# ATtinyBoard.net
KiCad netlist of a schematic drawn in EAGLE
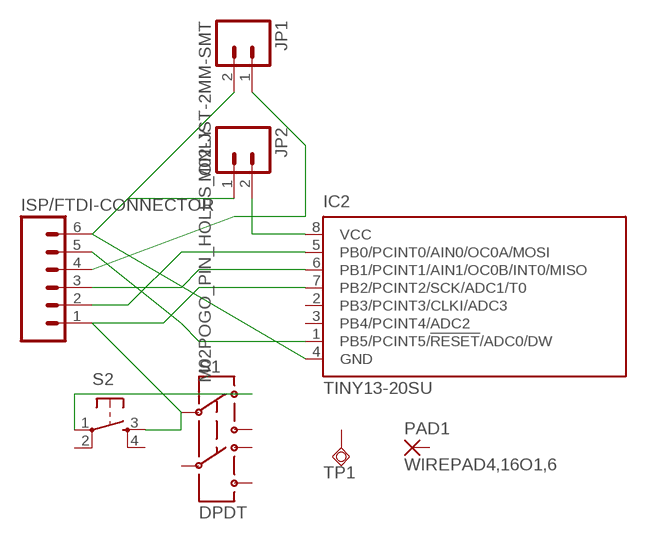
[diagram p0: schematic, sheet 1]

(export (version "E")
  (design (tool "Eeschema 10.0.6"))
  (components
    (comp (ref "IC2")
      (value "TINY13-20SU")
      (footprint "eagle-import:8S2")
      (fields (field (name "MPN") "ATTINY13-20SU"))
      (libsource (lib "eagle-import") (part "TINY13SU-20"))
    )
    (comp (ref "ISP/FTDI-CONNECTOR")
      (value "M06SMD")
      (footprint "eagle-import:1X06-SMD")
      (libsource (lib "eagle-import") (part "M06SMD"))
    )
    (comp (ref "JP1")
      (value "M02-JST-2MM-SMT")
      (footprint "eagle-import:JST-2-SMD")
      (libsource (lib "eagle-import") (part "M02-JST-2MM-SMT"))
    )
    (comp (ref "JP2")
      (value "M02POGO_PIN_HOLES_ONLY")
      (footprint "eagle-import:1X02_PP_HOLES_ONLY")
      (libsource (lib "eagle-import") (part "M02POGO_PIN_HOLES_ONLY"))
    )
    (comp (ref "PAD1")
      (value "WIREPAD4,16O1,6")
      (footprint "eagle-import:4,16O1,6")
      (libsource (lib "eagle-import") (part "WIREPAD4,16O1,6"))
    )
    (comp (ref "S1")
      (value "DPDT")
      (footprint "eagle-import:AYZ0202")
      (libsource (lib "eagle-import") (part "SWITCH-DPDTAYZ0202"))
    )
    (comp (ref "S2")
      (value "TAC_SWITCHSMD")
      (footprint "eagle-import:TACTILE_SWITCH_SMD")
      (libsource (lib "eagle-import") (part "TAC_SWITCHSMD"))
    )
    (comp (ref "TP1")
      (value "TPSQTP20R")
      (footprint "eagle-import:TP20R")
      (libsource (lib "eagle-import") (part "TPSQTP20R"))
    )
  )
  (nets
    (net (code "1") (name "Net-(IC2-GND)") (class "Default")
      (node (ref "IC2") (pin "4") (pinfunction "GND_4") (pintype "power_in"))
      (node (ref "ISP/FTDI-CONNECTOR") (pin "6") (pinfunction "6_6") (pintype "passive"))
      (node (ref "JP1") (pin "2") (pinfunction "1_2") (pintype "passive"))
      (node (ref "JP2") (pin "1") (pinfunction "1_1") (pintype "passive"))
    )
    (net (code "2") (name "Net-(IC2-PB0{slash}PCINT0{slash}AIN0{slash}OC0A{slash}MOSI)") (class "Default")
      (node (ref "IC2") (pin "5") (pinfunction "PB0/PCINT0/AIN0/OC0A/MOSI_5") (pintype "bidirectional"))
      (node (ref "ISP/FTDI-CONNECTOR") (pin "2") (pinfunction "2_2") (pintype "passive"))
    )
    (net (code "3") (name "Net-(IC2-PB1{slash}PCINT1{slash}AIN1{slash}OC0B{slash}INT0{slash}MISO)") (class "Default")
      (node (ref "IC2") (pin "6") (pinfunction "PB1/PCINT1/AIN1/OC0B/INT0/MISO_6") (pintype "bidirectional"))
      (node (ref "ISP/FTDI-CONNECTOR") (pin "3") (pinfunction "3_3") (pintype "passive"))
    )
    (net (code "4") (name "Net-(IC2-PB2{slash}PCINT2{slash}SCK{slash}ADC1{slash}T0)") (class "Default")
      (node (ref "IC2") (pin "7") (pinfunction "PB2/PCINT2/SCK/ADC1/T0_7") (pintype "bidirectional"))
      (node (ref "ISP/FTDI-CONNECTOR") (pin "1") (pinfunction "1_1") (pintype "passive"))
      (node (ref "S1") (pin "2") (pinfunction "2_2") (pintype "bidirectional"))
      (node (ref "S2") (pin "3") (pinfunction "3_3") (pintype "passive"))
    )
    (net (code "5") (name "Net-(IC2-PB5{slash}PCINT5{slash}~{RESET}{slash}ADC0{slash}DW)") (class "Default")
      (node (ref "IC2") (pin "1") (pinfunction "PB5/PCINT5/~{RESET}/ADC0/DW_1") (pintype "bidirectional"))
      (node (ref "ISP/FTDI-CONNECTOR") (pin "5") (pinfunction "5_5") (pintype "passive"))
    )
    (net (code "6") (name "Net-(IC2-VCC)") (class "Default")
      (node (ref "IC2") (pin "8") (pinfunction "VCC_8") (pintype "power_in"))
      (node (ref "ISP/FTDI-CONNECTOR") (pin "4") (pinfunction "4_4") (pintype "passive"))
      (node (ref "JP1") (pin "1") (pinfunction "2_1") (pintype "passive"))
      (node (ref "JP2") (pin "2") (pinfunction "2_2") (pintype "passive"))
    )
    (net (code "7") (name "Net-(S1-Pad1)") (class "Default")
      (node (ref "S1") (pin "1") (pinfunction "1_1") (pintype "bidirectional"))
      (node (ref "S2") (pin "1") (pinfunction "1_1") (pintype "passive"))
    )
    (net (code "8") (name "unconnected-(IC2-PB3{slash}PCINT3{slash}CLKI{slash}ADC3-Pad2)") (class "Default")
      (node (ref "IC2") (pin "2") (pinfunction "PB3/PCINT3/CLKI/ADC3_2") (pintype "bidirectional"))
    )
    (net (code "9") (name "unconnected-(IC2-PB4{slash}PCINT4{slash}ADC2-Pad3)") (class "Default")
      (node (ref "IC2") (pin "3") (pinfunction "PB4/PCINT4/ADC2_3") (pintype "bidirectional"))
    )
    (net (code "10") (name "unconnected-(PAD1-P-Pad1)") (class "Default")
      (node (ref "PAD1") (pin "1") (pinfunction "P_1") (pintype "passive"))
    )
    (net (code "11") (name "unconnected-(S1-Pad3)") (class "Default")
      (node (ref "S1") (pin "3") (pinfunction "3_3") (pintype "bidirectional"))
    )
    (net (code "12") (name "unconnected-(S1-Pad4)") (class "Default")
      (node (ref "S1") (pin "4") (pinfunction "4_4") (pintype "bidirectional"))
    )
    (net (code "13") (name "unconnected-(S1-Pad5)") (class "Default")
      (node (ref "S1") (pin "5") (pinfunction "5_5") (pintype "bidirectional"))
    )
    (net (code "14") (name "unconnected-(S1-Pad6)") (class "Default")
      (node (ref "S1") (pin "6") (pinfunction "6_6") (pintype "bidirectional"))
    )
    (net (code "15") (name "unconnected-(S2-Pad2)") (class "Default")
      (node (ref "S2") (pin "2") (pinfunction "2_2") (pintype "passive"))
    )
    (net (code "16") (name "unconnected-(S2-Pad4)") (class "Default")
      (node (ref "S2") (pin "4") (pinfunction "4_4") (pintype "passive"))
    )
    (net (code "17") (name "unconnected-(TP1-PadTP)") (class "Default")
      (node (ref "TP1") (pin "TP") (pinfunction "TP_TP") (pintype "input"))
    )
  )
)
